# Sheet3.net
KiCad netlist of a schematic drawn in Altium Designer
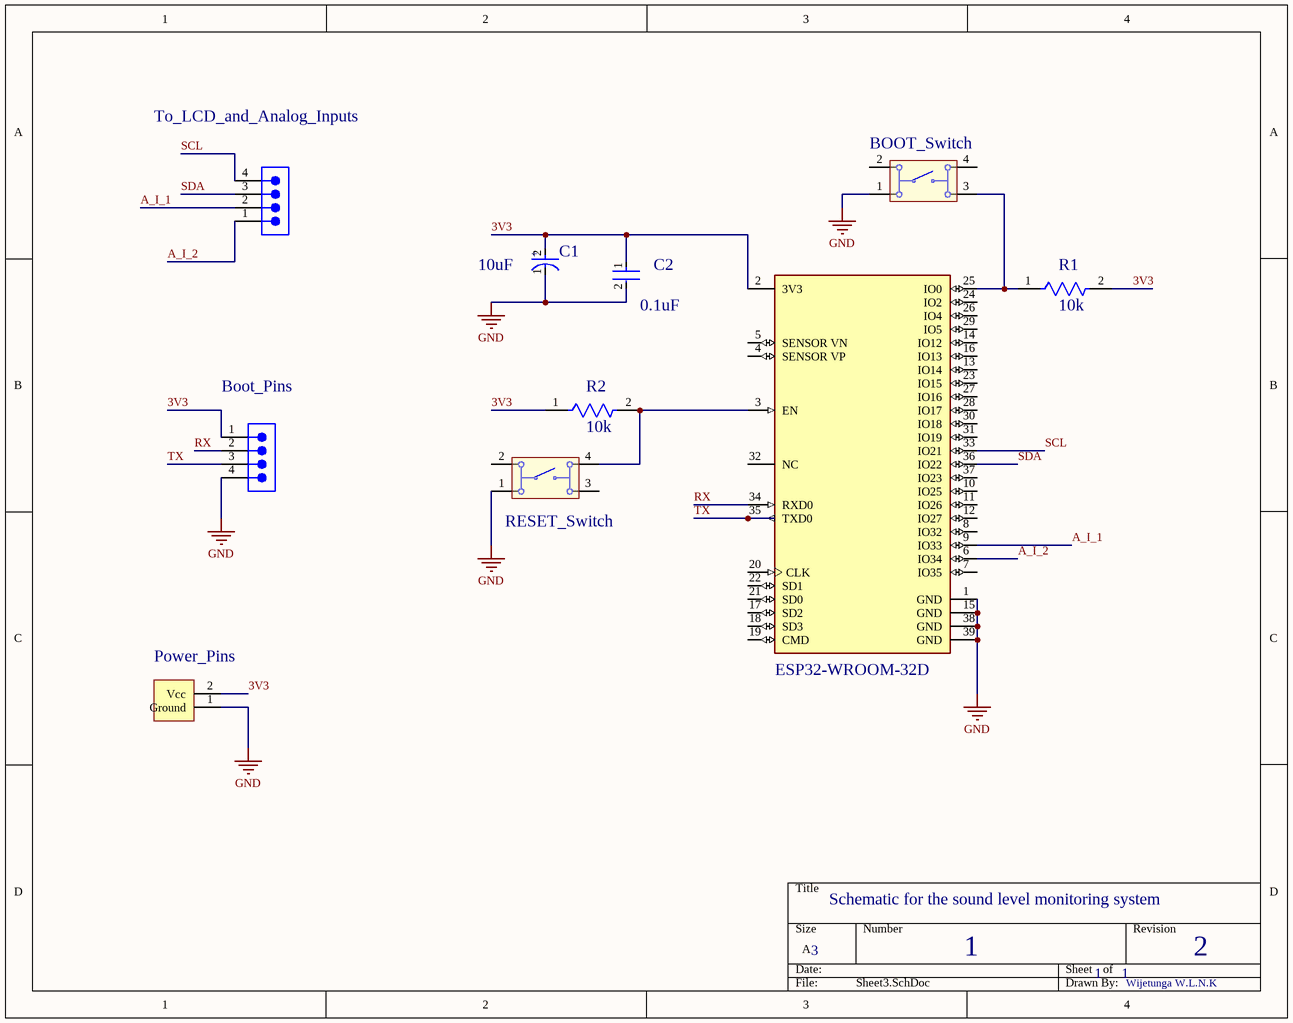
[diagram p0: Sheet3.SchDoc]

(export (version "E")
  (design (tool "Eeschema 10.0.6"))
  (components
    (comp (ref "Boot_Pins")
      (value "TSW-104-08-L-S")
      (footprint "SMTC-TSW-104-08-X-S")
      (description "0.025\" SQ Post Header, Through-hole, Vertical, -55 to 125 degC, 2.54 mm Pitch, 4-Pin, Male, RoHS")
      (fields (field (name "MANUFACTURER") "Samtec"))
      (libsource (lib "Altium Content Vault") (part "SMTC-TSW-104-08-X-S"))
    )
    (comp (ref "BOOT_Switch")
      (value "430471025826")
      (footprint "430471025826")
      (description "WS-TASV SMD Tact Switch 6X6 mm")
      (fields (field (name "MANUFACTURER") "Wuerth Elektronik"))
      (libsource (lib "Altium Content Vault") (part "WE-TACT-SW-4_A"))
    )
    (comp (ref "C1")
      (value "10uF")
      (footprint "FP-RAD-TH-D_10_0_5-L_16_1-MFG")
      (description "Aluminum Electrolytic Capacitors (Radial Lead Type) AEC-Q200 Qualified 1000uF ±20% 10V")
      (fields (field (name "VOLTAGE") "10V") (field (name "TOLERANCE") "20%"))
      (libsource (lib "Altium Content Vault") (part "a00bbbee19879c290e62620ae7e47b1"))
    )
    (comp (ref "C2")
      (value "0.1uF")
      (footprint "FP-RCE0DB-MFG")
      (description "Cap Ceramic 100nF 50V X7R ±10% Radial 2.5mm +125°C Ammo Pack")
      (fields (field (name "TOLERANCE") "10%"))
      (libsource (lib "Altium Content Vault") (part "b4654b650e69147ec39a6b967a45e02"))
    )
    (comp (ref "ESP32-WROOM-32D")
      (value "ESP32-WROOM-32D")
      (footprint "FP-ESP32-WROOM-32D-MFG")
      (description "WIFI MODULE 32MBITS SPI FLASH")
      (fields
        (field (name "OCTOPART") "https://octopart.com/esp32-wroom-32d-espressif+systems-91040050")
        (field (name "MANUFACTURER") "Espressif Systems")
      )
      (libsource (lib "Altium Content Vault") (part "a031a76f8c27026a7a7f4657ff233a3"))
    )
    (comp (ref "Power_Pins")
      (value "~")
      (footprint "HDR1X2")
      (description "Header, 2-Pin")
      (fields (field (name "PUBLISHER") "Altium Limited"))
      (libsource (lib "University of Moratuwa") (part "Header 2H"))
    )
    (comp (ref "R1")
      (value "10k")
      (footprint "FP-MBB0207-MFG")
      (description "RES 10K OHM 0.6W 1% AXIAL")
      (fields (field (name "TOLERANCE") "1%"))
      (libsource (lib "Altium Content Vault") (part "1029c3af85768c4190bb7ad29bc67b5"))
    )
    (comp (ref "R2")
      (value "10k")
      (footprint "FP-MBB0207-MFG")
      (description "RES 10K OHM 0.6W 1% AXIAL")
      (fields (field (name "TOLERANCE") "1%"))
      (libsource (lib "Altium Content Vault") (part "1029c3af85768c4190bb7ad29bc67b5"))
    )
    (comp (ref "RESET_Switch")
      (value "430471025826")
      (footprint "430471025826")
      (description "WS-TASV SMD Tact Switch 6X6 mm")
      (fields (field (name "MANUFACTURER") "Wuerth Elektronik"))
      (libsource (lib "Altium Content Vault") (part "WE-TACT-SW-4_A"))
    )
    (comp (ref "To_LCD_and_Analog_Inputs")
      (value "TSW-104-08-L-S")
      (footprint "SMTC-TSW-104-08-X-S")
      (description "0.025\" SQ Post Header, Through-hole, Vertical, -55 to 125 degC, 2.54 mm Pitch, 4-Pin, Male, RoHS")
      (fields (field (name "MANUFACTURER") "Samtec"))
      (libsource (lib "Altium Content Vault") (part "SMTC-TSW-104-08-X-S"))
    )
  )
  (nets
    (net (code "1") (name "/3V3") (class "Default")
      (node (ref "Boot_Pins") (pin "1") (pinfunction "1_1") (pintype "passive"))
      (node (ref "C1") (pin "2") (pinfunction "A_2") (pintype "passive"))
      (node (ref "C2") (pin "1") (pinfunction "1_1") (pintype "passive"))
      (node (ref "ESP32-WROOM-32D") (pin "2") (pinfunction "3V3_2") (pintype "power_in"))
      (node (ref "Power_Pins") (pin "2") (pinfunction "Vcc_2") (pintype "passive"))
      (node (ref "R1") (pin "2") (pinfunction "2_2") (pintype "passive"))
      (node (ref "R2") (pin "1") (pinfunction "1_1") (pintype "passive"))
    )
    (net (code "2") (name "/A_I_1") (class "Default")
      (node (ref "ESP32-WROOM-32D") (pin "9") (pinfunction "IO33_9") (pintype "bidirectional"))
      (node (ref "To_LCD_and_Analog_Inputs") (pin "2") (pinfunction "2_2") (pintype "passive"))
    )
    (net (code "3") (name "/A_I_2") (class "Default")
      (node (ref "ESP32-WROOM-32D") (pin "6") (pinfunction "IO34_6") (pintype "bidirectional"))
      (node (ref "To_LCD_and_Analog_Inputs") (pin "1") (pinfunction "1_1") (pintype "passive"))
    )
    (net (code "4") (name "/RX") (class "Default")
      (node (ref "Boot_Pins") (pin "2") (pinfunction "2_2") (pintype "passive"))
      (node (ref "ESP32-WROOM-32D") (pin "34") (pinfunction "RXD0_34") (pintype "input"))
    )
    (net (code "5") (name "/SCL") (class "Default")
      (node (ref "ESP32-WROOM-32D") (pin "33") (pinfunction "IO21_33") (pintype "bidirectional"))
      (node (ref "To_LCD_and_Analog_Inputs") (pin "4") (pinfunction "4_4") (pintype "passive"))
    )
    (net (code "6") (name "/SDA") (class "Default")
      (node (ref "ESP32-WROOM-32D") (pin "36") (pinfunction "IO22_36") (pintype "bidirectional"))
      (node (ref "To_LCD_and_Analog_Inputs") (pin "3") (pinfunction "3_3") (pintype "passive"))
    )
    (net (code "7") (name "/TX") (class "Default")
      (node (ref "Boot_Pins") (pin "3") (pinfunction "3_3") (pintype "passive"))
      (node (ref "ESP32-WROOM-32D") (pin "35") (pinfunction "TXD0_35") (pintype "output"))
    )
    (net (code "8") (name "GND") (class "Default")
      (node (ref "BOOT_Switch") (pin "1") (pinfunction "1_1") (pintype "passive"))
      (node (ref "Boot_Pins") (pin "4") (pinfunction "4_4") (pintype "passive"))
      (node (ref "C1") (pin "1") (pinfunction "C_1") (pintype "passive"))
      (node (ref "C2") (pin "2") (pinfunction "2_2") (pintype "passive"))
      (node (ref "ESP32-WROOM-32D") (pin "1") (pinfunction "GND_1") (pintype "power_in"))
      (node (ref "ESP32-WROOM-32D") (pin "15") (pinfunction "GND_15") (pintype "power_in"))
      (node (ref "ESP32-WROOM-32D") (pin "38") (pinfunction "GND_38") (pintype "power_in"))
      (node (ref "ESP32-WROOM-32D") (pin "39") (pinfunction "GND_39") (pintype "power_in"))
      (node (ref "Power_Pins") (pin "1") (pinfunction "Ground_1") (pintype "passive"))
      (node (ref "RESET_Switch") (pin "1") (pinfunction "1_1") (pintype "passive"))
    )
    (net (code "9") (name "Net-(ESP32-WROOM-32D-EN)") (class "Default")
      (node (ref "ESP32-WROOM-32D") (pin "3") (pinfunction "EN_3") (pintype "input"))
      (node (ref "R2") (pin "2") (pinfunction "2_2") (pintype "passive"))
      (node (ref "RESET_Switch") (pin "4") (pinfunction "4_4") (pintype "passive"))
    )
    (net (code "10") (name "Net-(ESP32-WROOM-32D-IO0)") (class "Default")
      (node (ref "BOOT_Switch") (pin "3") (pinfunction "3_3") (pintype "passive"))
      (node (ref "ESP32-WROOM-32D") (pin "25") (pinfunction "IO0_25") (pintype "bidirectional"))
      (node (ref "R1") (pin "1") (pinfunction "1_1") (pintype "passive"))
    )
    (net (code "11") (name "unconnected-(BOOT_Switch-Pad2)") (class "Default")
      (node (ref "BOOT_Switch") (pin "2") (pinfunction "2_2") (pintype "passive"))
    )
    (net (code "12") (name "unconnected-(BOOT_Switch-Pad4)") (class "Default")
      (node (ref "BOOT_Switch") (pin "4") (pinfunction "4_4") (pintype "passive"))
    )
    (net (code "13") (name "unconnected-(ESP32-WROOM-32D-CLK-Pad20)") (class "Default")
      (node (ref "ESP32-WROOM-32D") (pin "20") (pinfunction "CLK_20") (pintype "input"))
    )
    (net (code "14") (name "unconnected-(ESP32-WROOM-32D-CMD-Pad19)") (class "Default")
      (node (ref "ESP32-WROOM-32D") (pin "19") (pinfunction "CMD_19") (pintype "bidirectional"))
    )
    (net (code "15") (name "unconnected-(ESP32-WROOM-32D-IO2-Pad24)") (class "Default")
      (node (ref "ESP32-WROOM-32D") (pin "24") (pinfunction "IO2_24") (pintype "bidirectional"))
    )
    (net (code "16") (name "unconnected-(ESP32-WROOM-32D-IO4-Pad26)") (class "Default")
      (node (ref "ESP32-WROOM-32D") (pin "26") (pinfunction "IO4_26") (pintype "bidirectional"))
    )
    (net (code "17") (name "unconnected-(ESP32-WROOM-32D-IO5-Pad29)") (class "Default")
      (node (ref "ESP32-WROOM-32D") (pin "29") (pinfunction "IO5_29") (pintype "bidirectional"))
    )
    (net (code "18") (name "unconnected-(ESP32-WROOM-32D-IO12-Pad14)") (class "Default")
      (node (ref "ESP32-WROOM-32D") (pin "14") (pinfunction "IO12_14") (pintype "bidirectional"))
    )
    (net (code "19") (name "unconnected-(ESP32-WROOM-32D-IO13-Pad16)") (class "Default")
      (node (ref "ESP32-WROOM-32D") (pin "16") (pinfunction "IO13_16") (pintype "bidirectional"))
    )
    (net (code "20") (name "unconnected-(ESP32-WROOM-32D-IO14-Pad13)") (class "Default")
      (node (ref "ESP32-WROOM-32D") (pin "13") (pinfunction "IO14_13") (pintype "bidirectional"))
    )
    (net (code "21") (name "unconnected-(ESP32-WROOM-32D-IO15-Pad23)") (class "Default")
      (node (ref "ESP32-WROOM-32D") (pin "23") (pinfunction "IO15_23") (pintype "bidirectional"))
    )
    (net (code "22") (name "unconnected-(ESP32-WROOM-32D-IO16-Pad27)") (class "Default")
      (node (ref "ESP32-WROOM-32D") (pin "27") (pinfunction "IO16_27") (pintype "bidirectional"))
    )
    (net (code "23") (name "unconnected-(ESP32-WROOM-32D-IO17-Pad28)") (class "Default")
      (node (ref "ESP32-WROOM-32D") (pin "28") (pinfunction "IO17_28") (pintype "bidirectional"))
    )
    (net (code "24") (name "unconnected-(ESP32-WROOM-32D-IO18-Pad30)") (class "Default")
      (node (ref "ESP32-WROOM-32D") (pin "30") (pinfunction "IO18_30") (pintype "bidirectional"))
    )
    (net (code "25") (name "unconnected-(ESP32-WROOM-32D-IO19-Pad31)") (class "Default")
      (node (ref "ESP32-WROOM-32D") (pin "31") (pinfunction "IO19_31") (pintype "bidirectional"))
    )
    (net (code "26") (name "unconnected-(ESP32-WROOM-32D-IO23-Pad37)") (class "Default")
      (node (ref "ESP32-WROOM-32D") (pin "37") (pinfunction "IO23_37") (pintype "bidirectional"))
    )
    (net (code "27") (name "unconnected-(ESP32-WROOM-32D-IO25-Pad10)") (class "Default")
      (node (ref "ESP32-WROOM-32D") (pin "10") (pinfunction "IO25_10") (pintype "bidirectional"))
    )
    (net (code "28") (name "unconnected-(ESP32-WROOM-32D-IO26-Pad11)") (class "Default")
      (node (ref "ESP32-WROOM-32D") (pin "11") (pinfunction "IO26_11") (pintype "bidirectional"))
    )
    (net (code "29") (name "unconnected-(ESP32-WROOM-32D-IO27-Pad12)") (class "Default")
      (node (ref "ESP32-WROOM-32D") (pin "12") (pinfunction "IO27_12") (pintype "bidirectional"))
    )
    (net (code "30") (name "unconnected-(ESP32-WROOM-32D-IO32-Pad8)") (class "Default")
      (node (ref "ESP32-WROOM-32D") (pin "8") (pinfunction "IO32_8") (pintype "bidirectional"))
    )
    (net (code "31") (name "unconnected-(ESP32-WROOM-32D-IO35-Pad7)") (class "Default")
      (node (ref "ESP32-WROOM-32D") (pin "7") (pinfunction "IO35_7") (pintype "bidirectional"))
    )
    (net (code "32") (name "unconnected-(ESP32-WROOM-32D-NC-Pad32)") (class "Default")
      (node (ref "ESP32-WROOM-32D") (pin "32") (pinfunction "NC_32") (pintype "passive"))
    )
    (net (code "33") (name "unconnected-(ESP32-WROOM-32D-SD0-Pad21)") (class "Default")
      (node (ref "ESP32-WROOM-32D") (pin "21") (pinfunction "SD0_21") (pintype "bidirectional"))
    )
    (net (code "34") (name "unconnected-(ESP32-WROOM-32D-SD1-Pad22)") (class "Default")
      (node (ref "ESP32-WROOM-32D") (pin "22") (pinfunction "SD1_22") (pintype "bidirectional"))
    )
    (net (code "35") (name "unconnected-(ESP32-WROOM-32D-SD2-Pad17)") (class "Default")
      (node (ref "ESP32-WROOM-32D") (pin "17") (pinfunction "SD2_17") (pintype "bidirectional"))
    )
    (net (code "36") (name "unconnected-(ESP32-WROOM-32D-SD3-Pad18)") (class "Default")
      (node (ref "ESP32-WROOM-32D") (pin "18") (pinfunction "SD3_18") (pintype "bidirectional"))
    )
    (net (code "37") (name "unconnected-(ESP32-WROOM-32D-SENSOR_VN-Pad5)") (class "Default")
      (node (ref "ESP32-WROOM-32D") (pin "5") (pinfunction "SENSOR_VN_5") (pintype "bidirectional"))
    )
    (net (code "38") (name "unconnected-(ESP32-WROOM-32D-SENSOR_VP-Pad4)") (class "Default")
      (node (ref "ESP32-WROOM-32D") (pin "4") (pinfunction "SENSOR_VP_4") (pintype "bidirectional"))
    )
    (net (code "39") (name "unconnected-(RESET_Switch-Pad2)") (class "Default")
      (node (ref "RESET_Switch") (pin "2") (pinfunction "2_2") (pintype "passive"))
    )
    (net (code "40") (name "unconnected-(RESET_Switch-Pad3)") (class "Default")
      (node (ref "RESET_Switch") (pin "3") (pinfunction "3_3") (pintype "passive"))
    )
  )
)
